# Ethernet.net
KiCad netlist of a schematic drawn in Altium Designer
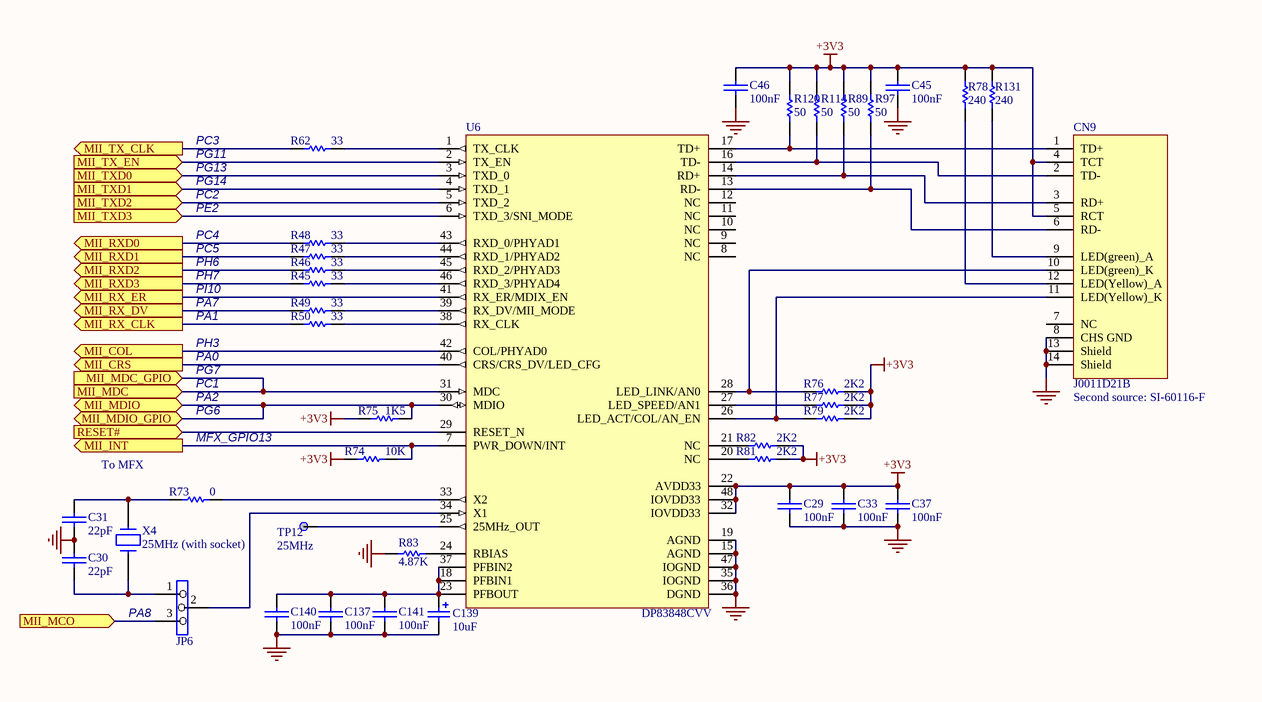
[diagram p0: Ethernet.SchDoc]

(export (version "E")
  (design (tool "Eeschema 10.0.6"))
  (components
    (comp (ref "C29")
      (value "100nF")
      (footprint "0603C")
      (description "Capacitor")
      (libsource (lib "*") (part "CAP"))
    )
    (comp (ref "C30")
      (value "22pF")
      (footprint "0603C")
      (description "Capacitor")
      (libsource (lib "*") (part "CAP"))
    )
    (comp (ref "C31")
      (value "22pF")
      (footprint "0603C")
      (description "Capacitor")
      (libsource (lib "*") (part "CAP"))
    )
    (comp (ref "C33")
      (value "100nF")
      (footprint "0603C")
      (description "Capacitor")
      (libsource (lib "*") (part "CAP"))
    )
    (comp (ref "C37")
      (value "100nF")
      (footprint "0603C")
      (description "Capacitor")
      (libsource (lib "*") (part "CAP"))
    )
    (comp (ref "C45")
      (value "100nF")
      (footprint "0603C")
      (description "Capacitor")
      (libsource (lib "*") (part "CAP"))
    )
    (comp (ref "C46")
      (value "100nF")
      (footprint "0603C")
      (description "Capacitor")
      (libsource (lib "*") (part "CAP"))
    )
    (comp (ref "C137")
      (value "100nF")
      (footprint "0603C")
      (description "Capacitor")
      (libsource (lib "*") (part "CAP"))
    )
    (comp (ref "C139")
      (value "10uF")
      (footprint "TAN-A")
      (description "Polarized Capacitor (Radial)")
      (fields (field (name "PUBLISHER") "Altium Limited"))
      (libsource (lib "Miscellaneous Devices") (part "Cap Pol1"))
    )
    (comp (ref "C140")
      (value "100nF")
      (footprint "0603C")
      (description "Capacitor")
      (libsource (lib "*") (part "CAP"))
    )
    (comp (ref "C141")
      (value "100nF")
      (footprint "0603C")
      (description "Capacitor")
      (libsource (lib "*") (part "CAP"))
    )
    (comp (ref "CN9")
      (value "J0011D21B")
      (footprint "RJ45_J0011D01BNL")
      (libsource (lib "MB784") (part "J0011D21B"))
    )
    (comp (ref "JP6") (value "~") (footprint "SIP3") (libsource (lib "STR910_SCHLIB") (part "Jumper3")))
    (comp (ref "R45")
      (value "33")
      (footprint "0603R")
      (description "Resistor")
      (fields (field (name "PUBLISHER") "Altium Limited"))
      (libsource (lib "Miscellaneous Devices") (part "Res1"))
    )
    (comp (ref "R46")
      (value "33")
      (footprint "0603R")
      (description "Resistor")
      (fields (field (name "PUBLISHER") "Altium Limited"))
      (libsource (lib "Miscellaneous Devices") (part "Res1"))
    )
    (comp (ref "R47")
      (value "33")
      (footprint "0603R")
      (description "Resistor")
      (fields (field (name "PUBLISHER") "Altium Limited"))
      (libsource (lib "Miscellaneous Devices") (part "Res1"))
    )
    (comp (ref "R48")
      (value "33")
      (footprint "0603R")
      (description "Resistor")
      (fields (field (name "PUBLISHER") "Altium Limited"))
      (libsource (lib "Miscellaneous Devices") (part "Res1"))
    )
    (comp (ref "R49")
      (value "33")
      (footprint "0603R")
      (description "Resistor")
      (fields (field (name "PUBLISHER") "Altium Limited"))
      (libsource (lib "Miscellaneous Devices") (part "Res1"))
    )
    (comp (ref "R50")
      (value "33")
      (footprint "0603R")
      (description "Resistor")
      (fields (field (name "PUBLISHER") "Altium Limited"))
      (libsource (lib "Miscellaneous Devices") (part "Res1"))
    )
    (comp (ref "R62")
      (value "33")
      (footprint "0603R")
      (description "Resistor")
      (fields (field (name "PUBLISHER") "Altium Limited"))
      (libsource (lib "Miscellaneous Devices") (part "Res1"))
    )
    (comp (ref "R73")
      (value "0")
      (footprint "0603R")
      (description "Resistor")
      (fields (field (name "PUBLISHER") "Altium Limited"))
      (libsource (lib "Miscellaneous Devices") (part "Res1"))
    )
    (comp (ref "R74")
      (value "10K")
      (footprint "0603R")
      (description "Resistor")
      (fields (field (name "PUBLISHER") "Altium Limited"))
      (libsource (lib "Miscellaneous Devices") (part "Res1"))
    )
    (comp (ref "R75")
      (value "1K5")
      (footprint "0603R")
      (description "Resistor")
      (fields (field (name "PUBLISHER") "Altium Limited"))
      (libsource (lib "Miscellaneous Devices") (part "Res1"))
    )
    (comp (ref "R76")
      (value "2K2")
      (footprint "0603R")
      (description "Resistor")
      (fields (field (name "PUBLISHER") "Altium Limited"))
      (libsource (lib "Miscellaneous Devices") (part "Res1"))
    )
    (comp (ref "R77")
      (value "2K2")
      (footprint "0603R")
      (description "Resistor")
      (fields (field (name "PUBLISHER") "Altium Limited"))
      (libsource (lib "Miscellaneous Devices") (part "Res1"))
    )
    (comp (ref "R78")
      (value "240")
      (footprint "0603R")
      (description "Resistor")
      (fields (field (name "PUBLISHER") "Altium Limited"))
      (libsource (lib "Miscellaneous Devices") (part "Res1"))
    )
    (comp (ref "R79")
      (value "2K2")
      (footprint "0603R")
      (description "Resistor")
      (fields (field (name "PUBLISHER") "Altium Limited"))
      (libsource (lib "Miscellaneous Devices") (part "Res1"))
    )
    (comp (ref "R81")
      (value "2K2")
      (footprint "0603R")
      (description "Resistor")
      (fields (field (name "PUBLISHER") "Altium Limited"))
      (libsource (lib "Miscellaneous Devices") (part "Res1"))
    )
    (comp (ref "R82")
      (value "2K2")
      (footprint "0603R")
      (description "Resistor")
      (fields (field (name "PUBLISHER") "Altium Limited"))
      (libsource (lib "Miscellaneous Devices") (part "Res1"))
    )
    (comp (ref "R83")
      (value "4.87K")
      (footprint "0603R")
      (description "Resistor")
      (fields (field (name "PUBLISHER") "Altium Limited"))
      (libsource (lib "Miscellaneous Devices") (part "Res1"))
    )
    (comp (ref "R89")
      (value "50")
      (footprint "0603R")
      (description "Resistor")
      (fields (field (name "PUBLISHER") "Altium Limited"))
      (libsource (lib "Miscellaneous Devices") (part "Res1"))
    )
    (comp (ref "R97")
      (value "50")
      (footprint "0603R")
      (description "Resistor")
      (fields (field (name "PUBLISHER") "Altium Limited"))
      (libsource (lib "Miscellaneous Devices") (part "Res1"))
    )
    (comp (ref "R114")
      (value "50")
      (footprint "0603R")
      (description "Resistor")
      (fields (field (name "PUBLISHER") "Altium Limited"))
      (libsource (lib "Miscellaneous Devices") (part "Res1"))
    )
    (comp (ref "R120")
      (value "50")
      (footprint "0603R")
      (description "Resistor")
      (fields (field (name "PUBLISHER") "Altium Limited"))
      (libsource (lib "Miscellaneous Devices") (part "Res1"))
    )
    (comp (ref "R131")
      (value "240")
      (footprint "0603R")
      (description "Resistor")
      (fields (field (name "PUBLISHER") "Altium Limited"))
      (libsource (lib "Miscellaneous Devices") (part "Res1"))
    )
    (comp (ref "TP12") (value "25MHz") (footprint "TP") (libsource (lib "*") (part "TP")))
    (comp (ref "U6")
      (value "DP83848CVV")
      (footprint "LQFP48_0R5_9X9")
      (libsource (lib "MB784") (part "DP83848CVV"))
    )
    (comp (ref "X4")
      (value "25MHz (with socket)")
      (footprint "XTAL_socket")
      (description "Crystal")
      (libsource (lib "*") (part "CRYSTAL"))
    )
  )
  (nets
    (net (code "1") (name "+3V3") (class "Default")
      (node (ref "C29") (pin "1") (pinfunction "1_1") (pintype "passive"))
      (node (ref "C33") (pin "2") (pinfunction "2_2") (pintype "passive"))
      (node (ref "C37") (pin "2") (pinfunction "2_2") (pintype "passive"))
      (node (ref "C45") (pin "2") (pinfunction "2_2") (pintype "passive"))
      (node (ref "C46") (pin "2") (pinfunction "2_2") (pintype "passive"))
      (node (ref "CN9") (pin "4") (pinfunction "TCT_4") (pintype "passive"))
      (node (ref "CN9") (pin "5") (pinfunction "RCT_5") (pintype "passive"))
      (node (ref "R114") (pin "1") (pinfunction "1_1") (pintype "passive"))
      (node (ref "R120") (pin "1") (pinfunction "1_1") (pintype "passive"))
      (node (ref "R131") (pin "2") (pinfunction "2_2") (pintype "passive"))
      (node (ref "R74") (pin "1") (pinfunction "1_1") (pintype "passive"))
      (node (ref "R75") (pin "2") (pinfunction "2_2") (pintype "passive"))
      (node (ref "R76") (pin "2") (pinfunction "2_2") (pintype "passive"))
      (node (ref "R77") (pin "2") (pinfunction "2_2") (pintype "passive"))
      (node (ref "R78") (pin "2") (pinfunction "2_2") (pintype "passive"))
      (node (ref "R79") (pin "2") (pinfunction "2_2") (pintype "passive"))
      (node (ref "R81") (pin "2") (pinfunction "2_2") (pintype "passive"))
      (node (ref "R82") (pin "2") (pinfunction "2_2") (pintype "passive"))
      (node (ref "R89") (pin "1") (pinfunction "1_1") (pintype "passive"))
      (node (ref "R97") (pin "1") (pinfunction "1_1") (pintype "passive"))
      (node (ref "U6") (pin "22") (pinfunction "AVDD33_22") (pintype "passive"))
      (node (ref "U6") (pin "32") (pinfunction "IOVDD33_32") (pintype "passive"))
      (node (ref "U6") (pin "48") (pinfunction "IOVDD33_48") (pintype "passive"))
    )
    (net (code "2") (name "/MII_COL") (class "Default")
      (node (ref "U6") (pin "42") (pinfunction "COL/PHYAD0_42") (pintype "output"))
    )
    (net (code "3") (name "/MII_CRS") (class "Default")
      (node (ref "U6") (pin "40") (pinfunction "CRS/CRS_DV/LED_CFG_40") (pintype "output"))
    )
    (net (code "4") (name "/MII_INT") (class "Default")
      (node (ref "R74") (pin "2") (pinfunction "2_2") (pintype "passive"))
      (node (ref "U6") (pin "7") (pinfunction "PWR_DOWN/INT_7") (pintype "passive"))
    )
    (net (code "5") (name "/MII_MCO") (class "Default") (node (ref "JP6") (pin "3") (pintype "passive")))
    (net (code "6") (name "/MII_MDC") (class "Default")
      (node (ref "U6") (pin "31") (pinfunction "MDC_31") (pintype "input"))
    )
    (net (code "7") (name "/MII_MDIO") (class "Default")
      (node (ref "R75") (pin "1") (pinfunction "1_1") (pintype "passive"))
      (node (ref "U6") (pin "30") (pinfunction "MDIO_30") (pintype "bidirectional"))
    )
    (net (code "8") (name "/MII_RXD0") (class "Default")
      (node (ref "R48") (pin "2") (pinfunction "2_2") (pintype "passive"))
    )
    (net (code "9") (name "/MII_RXD1") (class "Default")
      (node (ref "R47") (pin "2") (pinfunction "2_2") (pintype "passive"))
    )
    (net (code "10") (name "/MII_RXD2") (class "Default")
      (node (ref "R46") (pin "2") (pinfunction "2_2") (pintype "passive"))
    )
    (net (code "11") (name "/MII_RXD3") (class "Default")
      (node (ref "R45") (pin "2") (pinfunction "2_2") (pintype "passive"))
    )
    (net (code "12") (name "/MII_RX_CLK") (class "Default")
      (node (ref "R50") (pin "2") (pinfunction "2_2") (pintype "passive"))
    )
    (net (code "13") (name "/MII_RX_DV") (class "Default")
      (node (ref "R49") (pin "2") (pinfunction "2_2") (pintype "passive"))
    )
    (net (code "14") (name "/MII_RX_ER") (class "Default")
      (node (ref "U6") (pin "41") (pinfunction "RX_ER/MDIX_EN_41") (pintype "output"))
    )
    (net (code "15") (name "/MII_TXD0") (class "Default")
      (node (ref "U6") (pin "3") (pinfunction "TXD_0_3") (pintype "input"))
    )
    (net (code "16") (name "/MII_TXD1") (class "Default")
      (node (ref "U6") (pin "4") (pinfunction "TXD_1_4") (pintype "input"))
    )
    (net (code "17") (name "/MII_TXD2") (class "Default")
      (node (ref "U6") (pin "5") (pinfunction "TXD_2_5") (pintype "input"))
    )
    (net (code "18") (name "/MII_TXD3") (class "Default")
      (node (ref "U6") (pin "6") (pinfunction "TXD_3/SNI_MODE_6") (pintype "input"))
    )
    (net (code "19") (name "/MII_TX_CLK") (class "Default")
      (node (ref "R62") (pin "2") (pinfunction "2_2") (pintype "passive"))
    )
    (net (code "20") (name "/MII_TX_EN") (class "Default")
      (node (ref "U6") (pin "2") (pinfunction "TX_EN_2") (pintype "input"))
    )
    (net (code "21") (name "/RESET#") (class "Default")
      (node (ref "U6") (pin "29") (pinfunction "RESET_N_29") (pintype "passive"))
    )
    (net (code "22") (name "GND") (class "Default")
      (node (ref "C137") (pin "1") (pinfunction "1_1") (pintype "passive"))
      (node (ref "C139") (pin "2") (pinfunction "2_2") (pintype "passive"))
      (node (ref "C140") (pin "2") (pinfunction "2_2") (pintype "passive"))
      (node (ref "C141") (pin "1") (pinfunction "1_1") (pintype "passive"))
      (node (ref "C29") (pin "2") (pinfunction "2_2") (pintype "passive"))
      (node (ref "C30") (pin "2") (pinfunction "2_2") (pintype "passive"))
      (node (ref "C31") (pin "1") (pinfunction "1_1") (pintype "passive"))
      (node (ref "C33") (pin "1") (pinfunction "1_1") (pintype "passive"))
      (node (ref "C37") (pin "1") (pinfunction "1_1") (pintype "passive"))
      (node (ref "C45") (pin "1") (pinfunction "1_1") (pintype "passive"))
      (node (ref "C46") (pin "1") (pinfunction "1_1") (pintype "passive"))
      (node (ref "CN9") (pin "13") (pinfunction "Shield_13") (pintype "passive"))
      (node (ref "CN9") (pin "14") (pinfunction "Shield_14") (pintype "passive"))
      (node (ref "CN9") (pin "8") (pinfunction "CHS_GND_8") (pintype "passive"))
      (node (ref "R83") (pin "1") (pinfunction "1_1") (pintype "passive"))
      (node (ref "U6") (pin "15") (pinfunction "AGND_15") (pintype "passive"))
      (node (ref "U6") (pin "19") (pinfunction "AGND_19") (pintype "passive"))
      (node (ref "U6") (pin "35") (pinfunction "IOGND_35") (pintype "passive"))
      (node (ref "U6") (pin "36") (pinfunction "DGND_36") (pintype "passive"))
      (node (ref "U6") (pin "47") (pinfunction "IOGND_47") (pintype "passive"))
    )
    (net (code "23") (name "Net-(C30-Pad1)") (class "Default")
      (node (ref "C30") (pin "1") (pinfunction "1_1") (pintype "passive"))
      (node (ref "JP6") (pin "1") (pintype "passive"))
      (node (ref "X4") (pin "1") (pinfunction "1_1") (pintype "passive"))
    )
    (net (code "24") (name "Net-(C31-Pad2)") (class "Default")
      (node (ref "C31") (pin "2") (pinfunction "2_2") (pintype "passive"))
      (node (ref "R73") (pin "2") (pinfunction "2_2") (pintype "passive"))
      (node (ref "X4") (pin "2") (pinfunction "2_2") (pintype "passive"))
    )
    (net (code "25") (name "Net-(CN9-LED(Yellow)_A)") (class "Default")
      (node (ref "CN9") (pin "12") (pinfunction "LED(Yellow)_A_12") (pintype "passive"))
      (node (ref "R78") (pin "1") (pinfunction "1_1") (pintype "passive"))
    )
    (net (code "26") (name "Net-(CN9-LED(Yellow)_K)") (class "Default")
      (node (ref "CN9") (pin "11") (pinfunction "LED(Yellow)_K_11") (pintype "passive"))
      (node (ref "R79") (pin "1") (pinfunction "1_1") (pintype "passive"))
      (node (ref "U6") (pin "26") (pinfunction "LED_ACT/COL/AN_EN_26") (pintype "passive"))
    )
    (net (code "27") (name "Net-(CN9-LED(green)_A)") (class "Default")
      (node (ref "CN9") (pin "9") (pinfunction "LED(green)_A_9") (pintype "passive"))
      (node (ref "R131") (pin "1") (pinfunction "1_1") (pintype "passive"))
    )
    (net (code "28") (name "Net-(CN9-LED(green)_K)") (class "Default")
      (node (ref "CN9") (pin "10") (pinfunction "LED(green)_K_10") (pintype "passive"))
      (node (ref "R76") (pin "1") (pinfunction "1_1") (pintype "passive"))
      (node (ref "U6") (pin "28") (pinfunction "LED_LINK/AN0_28") (pintype "passive"))
    )
    (net (code "29") (name "Net-(CN9-RD+)") (class "Default")
      (node (ref "CN9") (pin "3") (pinfunction "RD+_3") (pintype "passive"))
      (node (ref "R89") (pin "2") (pinfunction "2_2") (pintype "passive"))
      (node (ref "U6") (pin "14") (pinfunction "RD+_14") (pintype "passive"))
    )
    (net (code "30") (name "Net-(CN9-RD-)") (class "Default")
      (node (ref "CN9") (pin "6") (pinfunction "RD-_6") (pintype "passive"))
      (node (ref "R97") (pin "2") (pinfunction "2_2") (pintype "passive"))
      (node (ref "U6") (pin "13") (pinfunction "RD-_13") (pintype "passive"))
    )
    (net (code "31") (name "Net-(CN9-TD+)") (class "Default")
      (node (ref "CN9") (pin "1") (pinfunction "TD+_1") (pintype "passive"))
      (node (ref "R120") (pin "2") (pinfunction "2_2") (pintype "passive"))
      (node (ref "U6") (pin "17") (pinfunction "TD+_17") (pintype "passive"))
    )
    (net (code "32") (name "Net-(CN9-TD-)") (class "Default")
      (node (ref "CN9") (pin "2") (pinfunction "TD-_2") (pintype "passive"))
      (node (ref "R114") (pin "2") (pinfunction "2_2") (pintype "passive"))
      (node (ref "U6") (pin "16") (pinfunction "TD-_16") (pintype "passive"))
    )
    (net (code "33") (name "Net-(R81-Pad1)") (class "Default")
      (node (ref "R81") (pin "1") (pinfunction "1_1") (pintype "passive"))
      (node (ref "U6") (pin "20") (pinfunction "NC_20") (pintype "passive"))
    )
    (net (code "34") (name "Net-(R82-Pad1)") (class "Default")
      (node (ref "R82") (pin "1") (pinfunction "1_1") (pintype "passive"))
      (node (ref "U6") (pin "21") (pinfunction "NC_21") (pintype "passive"))
    )
    (net (code "35") (name "Net-(U6-25MHz_OUT)") (class "Default")
      (node (ref "TP12") (pin "1") (pinfunction "1_1") (pintype "passive"))
      (node (ref "U6") (pin "25") (pinfunction "25MHz_OUT_25") (pintype "output"))
    )
    (net (code "36") (name "Net-(U6-LED_SPEED{slash}AN1)") (class "Default")
      (node (ref "R77") (pin "1") (pinfunction "1_1") (pintype "passive"))
      (node (ref "U6") (pin "27") (pinfunction "LED_SPEED/AN1_27") (pintype "passive"))
    )
    (net (code "37") (name "Net-(U6-PFBIN1)") (class "Default")
      (node (ref "C137") (pin "2") (pinfunction "2_2") (pintype "passive"))
      (node (ref "C139") (pin "1") (pinfunction "1_1") (pintype "passive"))
      (node (ref "C140") (pin "1") (pinfunction "1_1") (pintype "passive"))
      (node (ref "C141") (pin "2") (pinfunction "2_2") (pintype "passive"))
      (node (ref "U6") (pin "18") (pinfunction "PFBIN1_18") (pintype "passive"))
      (node (ref "U6") (pin "23") (pinfunction "PFBOUT_23") (pintype "passive"))
      (node (ref "U6") (pin "37") (pinfunction "PFBIN2_37") (pintype "passive"))
    )
    (net (code "38") (name "Net-(U6-RBIAS)") (class "Default")
      (node (ref "R83") (pin "2") (pinfunction "2_2") (pintype "passive"))
      (node (ref "U6") (pin "24") (pinfunction "RBIAS_24") (pintype "passive"))
    )
    (net (code "39") (name "Net-(U6-RXD_0{slash}PHYAD1)") (class "Default")
      (node (ref "R48") (pin "1") (pinfunction "1_1") (pintype "passive"))
      (node (ref "U6") (pin "43") (pinfunction "RXD_0/PHYAD1_43") (pintype "output"))
    )
    (net (code "40") (name "Net-(U6-RXD_1{slash}PHYAD2)") (class "Default")
      (node (ref "R47") (pin "1") (pinfunction "1_1") (pintype "passive"))
      (node (ref "U6") (pin "44") (pinfunction "RXD_1/PHYAD2_44") (pintype "output"))
    )
    (net (code "41") (name "Net-(U6-RXD_2{slash}PHYAD3)") (class "Default")
      (node (ref "R46") (pin "1") (pinfunction "1_1") (pintype "passive"))
      (node (ref "U6") (pin "45") (pinfunction "RXD_2/PHYAD3_45") (pintype "output"))
    )
    (net (code "42") (name "Net-(U6-RXD_3{slash}PHYAD4)") (class "Default")
      (node (ref "R45") (pin "1") (pinfunction "1_1") (pintype "passive"))
      (node (ref "U6") (pin "46") (pinfunction "RXD_3/PHYAD4_46") (pintype "output"))
    )
    (net (code "43") (name "Net-(U6-RX_CLK)") (class "Default")
      (node (ref "R50") (pin "1") (pinfunction "1_1") (pintype "passive"))
      (node (ref "U6") (pin "38") (pinfunction "RX_CLK_38") (pintype "output"))
    )
    (net (code "44") (name "Net-(U6-RX_DV{slash}MII_MODE)") (class "Default")
      (node (ref "R49") (pin "1") (pinfunction "1_1") (pintype "passive"))
      (node (ref "U6") (pin "39") (pinfunction "RX_DV/MII_MODE_39") (pintype "output"))
    )
    (net (code "45") (name "Net-(U6-TX_CLK)") (class "Default")
      (node (ref "R62") (pin "1") (pinfunction "1_1") (pintype "passive"))
      (node (ref "U6") (pin "1") (pinfunction "TX_CLK_1") (pintype "output"))
    )
    (net (code "46") (name "Net-(U6-X1)") (class "Default")
      (node (ref "JP6") (pin "2") (pintype "passive"))
      (node (ref "U6") (pin "34") (pinfunction "X1_34") (pintype "input"))
    )
    (net (code "47") (name "Net-(U6-X2)") (class "Default")
      (node (ref "R73") (pin "1") (pinfunction "1_1") (pintype "passive"))
      (node (ref "U6") (pin "33") (pinfunction "X2_33") (pintype "output"))
    )
    (net (code "48") (name "unconnected-(CN9-NC-Pad7)") (class "Default")
      (node (ref "CN9") (pin "7") (pinfunction "NC_7") (pintype "passive"))
    )
    (net (code "49") (name "unconnected-(U6-NC-Pad8)") (class "Default")
      (node (ref "U6") (pin "8") (pinfunction "NC_8") (pintype "passive"))
    )
    (net (code "50") (name "unconnected-(U6-NC-Pad9)") (class "Default")
      (node (ref "U6") (pin "9") (pinfunction "NC_9") (pintype "passive"))
    )
    (net (code "51") (name "unconnected-(U6-NC-Pad10)") (class "Default")
      (node (ref "U6") (pin "10") (pinfunction "NC_10") (pintype "passive"))
    )
    (net (code "52") (name "unconnected-(U6-NC-Pad11)") (class "Default")
      (node (ref "U6") (pin "11") (pinfunction "NC_11") (pintype "passive"))
    )
    (net (code "53") (name "unconnected-(U6-NC-Pad12)") (class "Default")
      (node (ref "U6") (pin "12") (pinfunction "NC_12") (pintype "passive"))
    )
  )
)
